# CYM1A113.net
KiCad netlist of a schematic drawn in EAGLE
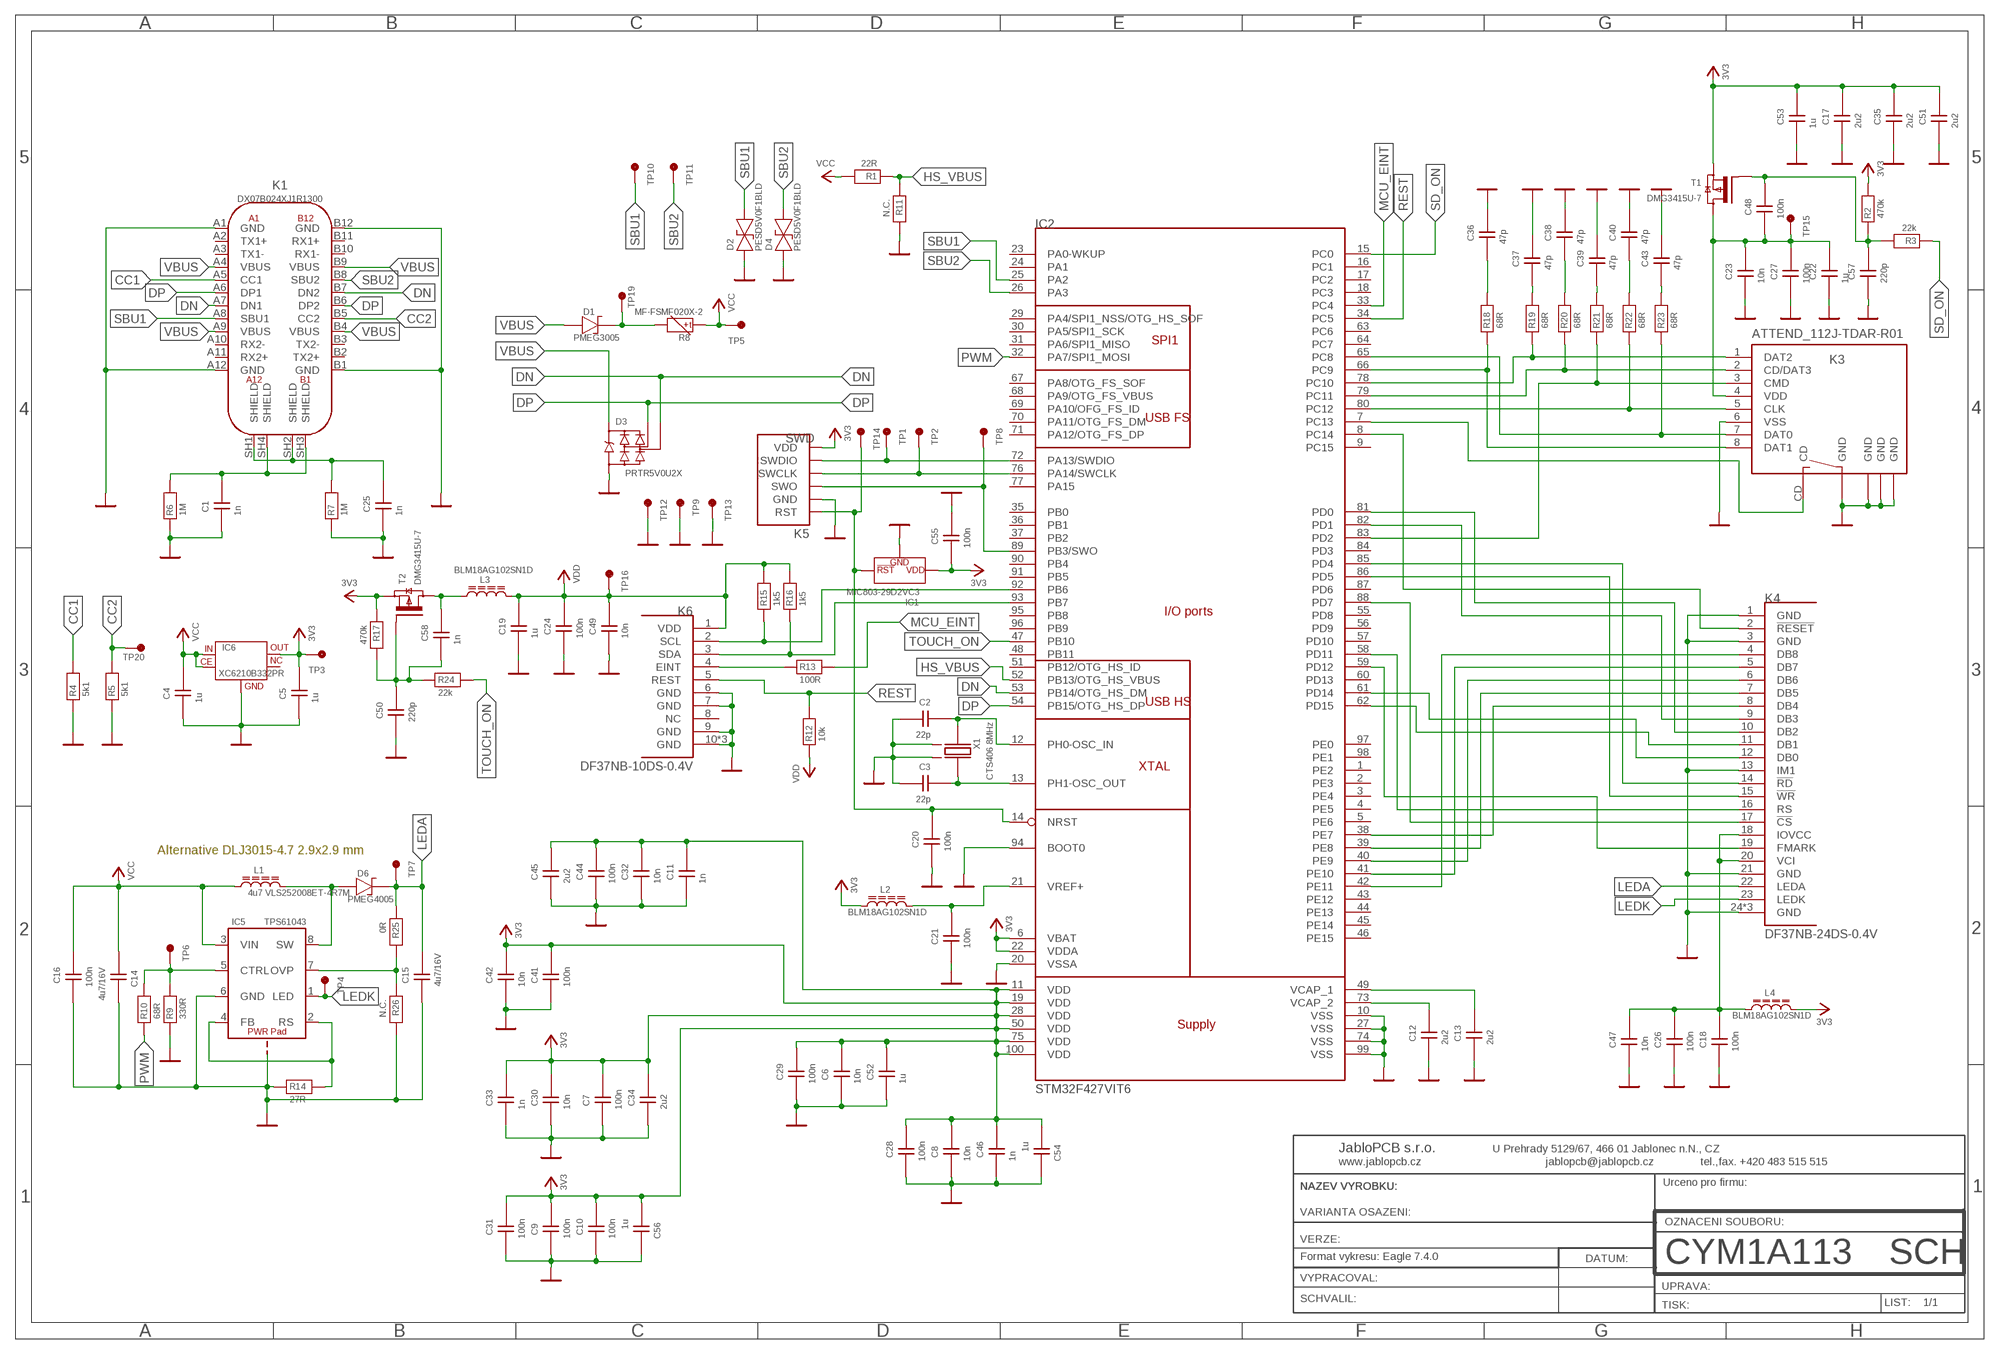
[diagram p0: schematic, sheet 1]

(export (version "E")
  (design (tool "Eeschema 10.0.6"))
  (components
    (comp (ref "C1")
      (value "1n")
      (footprint "eagle-import:0402")
      (libsource (lib "eagle-import") (part "C_0402"))
    )
    (comp (ref "C2")
      (value "22p")
      (footprint "eagle-import:0402")
      (libsource (lib "eagle-import") (part "C_0402"))
    )
    (comp (ref "C3")
      (value "22p")
      (footprint "eagle-import:0402")
      (libsource (lib "eagle-import") (part "C_0402"))
    )
    (comp (ref "C4")
      (value "1u")
      (footprint "eagle-import:0603_REFLOW")
      (libsource (lib "eagle-import") (part "C_0603$REFLOW"))
    )
    (comp (ref "C5")
      (value "1u")
      (footprint "eagle-import:0603")
      (libsource (lib "eagle-import") (part "C_0603"))
    )
    (comp (ref "C6")
      (value "10n")
      (footprint "eagle-import:0402")
      (libsource (lib "eagle-import") (part "C_0402"))
    )
    (comp (ref "C7")
      (value "100n")
      (footprint "eagle-import:0402")
      (libsource (lib "eagle-import") (part "C_0402"))
    )
    (comp (ref "C8")
      (value "10n")
      (footprint "eagle-import:0402")
      (libsource (lib "eagle-import") (part "C_0402"))
    )
    (comp (ref "C9")
      (value "100n")
      (footprint "eagle-import:0402")
      (libsource (lib "eagle-import") (part "C_0402"))
    )
    (comp (ref "C10")
      (value "100n")
      (footprint "eagle-import:0402")
      (libsource (lib "eagle-import") (part "C_0402"))
    )
    (comp (ref "C11")
      (value "1n")
      (footprint "eagle-import:0402")
      (libsource (lib "eagle-import") (part "C_0402"))
    )
    (comp (ref "C12")
      (value "2u2")
      (footprint "eagle-import:0805_REFLOW")
      (libsource (lib "eagle-import") (part "C_0805$REFLOW"))
    )
    (comp (ref "C13")
      (value "2u2")
      (footprint "eagle-import:0805_REFLOW")
      (libsource (lib "eagle-import") (part "C_0805$REFLOW"))
    )
    (comp (ref "C14")
      (value "4u7/16V")
      (footprint "eagle-import:0805_REFLOW")
      (libsource (lib "eagle-import") (part "C_0805$REFLOW"))
    )
    (comp (ref "C15")
      (value "4u7/16V")
      (footprint "eagle-import:0805_REFLOW")
      (libsource (lib "eagle-import") (part "C_0805$REFLOW"))
    )
    (comp (ref "C16")
      (value "100n")
      (footprint "eagle-import:0402")
      (libsource (lib "eagle-import") (part "C_0402"))
    )
    (comp (ref "C17")
      (value "2u2")
      (footprint "eagle-import:0805_REFLOW")
      (libsource (lib "eagle-import") (part "C_0805$REFLOW"))
    )
    (comp (ref "C18")
      (value "100n")
      (footprint "eagle-import:0402")
      (libsource (lib "eagle-import") (part "C_0402"))
    )
    (comp (ref "C19")
      (value "1u")
      (footprint "eagle-import:0603_REFLOW")
      (libsource (lib "eagle-import") (part "C_0603$REFLOW"))
    )
    (comp (ref "C20")
      (value "100n")
      (footprint "eagle-import:0402")
      (libsource (lib "eagle-import") (part "C_0402"))
    )
    (comp (ref "C21")
      (value "100n")
      (footprint "eagle-import:0402")
      (libsource (lib "eagle-import") (part "C_0402"))
    )
    (comp (ref "C22")
      (value "1u")
      (footprint "eagle-import:0603_REFLOW")
      (libsource (lib "eagle-import") (part "C_0603$REFLOW"))
    )
    (comp (ref "C23")
      (value "10n")
      (footprint "eagle-import:0402")
      (libsource (lib "eagle-import") (part "C_0402"))
    )
    (comp (ref "C24")
      (value "100n")
      (footprint "eagle-import:0402")
      (libsource (lib "eagle-import") (part "C_0402"))
    )
    (comp (ref "C25")
      (value "1n")
      (footprint "eagle-import:0402")
      (libsource (lib "eagle-import") (part "C_0402"))
    )
    (comp (ref "C26")
      (value "100n")
      (footprint "eagle-import:0402")
      (libsource (lib "eagle-import") (part "C_0402"))
    )
    (comp (ref "C27")
      (value "100n")
      (footprint "eagle-import:0402")
      (libsource (lib "eagle-import") (part "C_0402"))
    )
    (comp (ref "C28")
      (value "100n")
      (footprint "eagle-import:0402")
      (libsource (lib "eagle-import") (part "C_0402"))
    )
    (comp (ref "C29")
      (value "100n")
      (footprint "eagle-import:0402")
      (libsource (lib "eagle-import") (part "C_0402"))
    )
    (comp (ref "C30")
      (value "10n")
      (footprint "eagle-import:0402")
      (libsource (lib "eagle-import") (part "C_0402"))
    )
    (comp (ref "C31")
      (value "100n")
      (footprint "eagle-import:0402")
      (libsource (lib "eagle-import") (part "C_0402"))
    )
    (comp (ref "C32")
      (value "10n")
      (footprint "eagle-import:0402")
      (libsource (lib "eagle-import") (part "C_0402"))
    )
    (comp (ref "C33")
      (value "1n")
      (footprint "eagle-import:0402")
      (libsource (lib "eagle-import") (part "C_0402"))
    )
    (comp (ref "C34")
      (value "2u2")
      (footprint "eagle-import:0805_REFLOW")
      (libsource (lib "eagle-import") (part "C_0805$REFLOW"))
    )
    (comp (ref "C35")
      (value "2u2")
      (footprint "eagle-import:0805_REFLOW")
      (libsource (lib "eagle-import") (part "C_0805$REFLOW"))
    )
    (comp (ref "C36")
      (value "47p")
      (footprint "eagle-import:0402")
      (libsource (lib "eagle-import") (part "C_0402"))
    )
    (comp (ref "C37")
      (value "47p")
      (footprint "eagle-import:0402")
      (libsource (lib "eagle-import") (part "C_0402"))
    )
    (comp (ref "C38")
      (value "47p")
      (footprint "eagle-import:0402")
      (libsource (lib "eagle-import") (part "C_0402"))
    )
    (comp (ref "C39")
      (value "47p")
      (footprint "eagle-import:0402")
      (libsource (lib "eagle-import") (part "C_0402"))
    )
    (comp (ref "C40")
      (value "47p")
      (footprint "eagle-import:0402")
      (libsource (lib "eagle-import") (part "C_0402"))
    )
    (comp (ref "C41")
      (value "100n")
      (footprint "eagle-import:0402")
      (libsource (lib "eagle-import") (part "C_0402"))
    )
    (comp (ref "C42")
      (value "10n")
      (footprint "eagle-import:0402")
      (libsource (lib "eagle-import") (part "C_0402"))
    )
    (comp (ref "C43")
      (value "47p")
      (footprint "eagle-import:0402")
      (libsource (lib "eagle-import") (part "C_0402"))
    )
    (comp (ref "C44")
      (value "100n")
      (footprint "eagle-import:0402")
      (libsource (lib "eagle-import") (part "C_0402"))
    )
    (comp (ref "C45")
      (value "2u2")
      (footprint "eagle-import:0805_REFLOW")
      (libsource (lib "eagle-import") (part "C_0805$REFLOW"))
    )
    (comp (ref "C46")
      (value "1n")
      (footprint "eagle-import:0402")
      (libsource (lib "eagle-import") (part "C_0402"))
    )
    (comp (ref "C47")
      (value "10n")
      (footprint "eagle-import:0402")
      (libsource (lib "eagle-import") (part "C_0402"))
    )
    (comp (ref "C48")
      (value "100n")
      (footprint "eagle-import:0402")
      (libsource (lib "eagle-import") (part "C_0402"))
    )
    (comp (ref "C49")
      (value "10n")
      (footprint "eagle-import:0402")
      (libsource (lib "eagle-import") (part "C_0402"))
    )
    (comp (ref "C50")
      (value "220p")
      (footprint "eagle-import:0402")
      (libsource (lib "eagle-import") (part "C_0402"))
    )
    (comp (ref "C51")
      (value "2u2")
      (footprint "eagle-import:0805_REFLOW")
      (libsource (lib "eagle-import") (part "C_0805$REFLOW"))
    )
    (comp (ref "C52")
      (value "1u")
      (footprint "eagle-import:0603_REFLOW")
      (libsource (lib "eagle-import") (part "C_0603$REFLOW"))
    )
    (comp (ref "C53")
      (value "1u")
      (footprint "eagle-import:0603_REFLOW")
      (libsource (lib "eagle-import") (part "C_0603$REFLOW"))
    )
    (comp (ref "C54")
      (value "1u")
      (footprint "eagle-import:0603_REFLOW")
      (libsource (lib "eagle-import") (part "C_0603$REFLOW"))
    )
    (comp (ref "C55")
      (value "100n")
      (footprint "eagle-import:0402")
      (libsource (lib "eagle-import") (part "C_0402"))
    )
    (comp (ref "C56")
      (value "1u")
      (footprint "eagle-import:0603_REFLOW")
      (libsource (lib "eagle-import") (part "C_0603$REFLOW"))
    )
    (comp (ref "C57")
      (value "220p")
      (footprint "eagle-import:0402")
      (libsource (lib "eagle-import") (part "C_0402"))
    )
    (comp (ref "C58")
      (value "1n")
      (footprint "eagle-import:0402")
      (libsource (lib "eagle-import") (part "C_0402"))
    )
    (comp (ref "D1")
      (value "PMEG3005")
      (footprint "eagle-import:SOD323F")
      (libsource (lib "eagle-import") (part "DS_SOD323F"))
    )
    (comp (ref "D2")
      (value "PESD5V0F1BLD")
      (footprint "eagle-import:SOD882D")
      (libsource (lib "eagle-import") (part "D_TRANSIL_BI_SOD882D"))
    )
    (comp (ref "D3")
      (value "PRTR5V0U2X")
      (footprint "eagle-import:SOT143B_REFLOW")
      (libsource (lib "eagle-import") (part "PRTR5V0_SOT143B$REFLOW"))
    )
    (comp (ref "D4")
      (value "PESD5V0F1BLD")
      (footprint "eagle-import:SOD882D")
      (libsource (lib "eagle-import") (part "D_TRANSIL_BI_SOD882D"))
    )
    (comp (ref "D6")
      (value "PMEG4005")
      (footprint "eagle-import:SOD323F")
      (libsource (lib "eagle-import") (part "DS_SOD323F"))
    )
    (comp (ref "IC1")
      (value "MIC803-29D2VC3")
      (footprint "eagle-import:SOT23_MEDIUM_SIZE")
      (libsource (lib "eagle-import") (part "MIC803"))
    )
    (comp (ref "IC2")
      (value "STM32F427VIT6")
      (footprint "eagle-import:LQFP100_NO_CENTER_NO_TDOCU")
      (libsource (lib "eagle-import") (part "STM32F427_LQFP100"))
    )
    (comp (ref "IC5")
      (value "TPS61043")
      (footprint "eagle-import:WSON-8_3X3MM")
      (libsource (lib "eagle-import") (part "TP6104X_WSON-8_3X3MM"))
    )
    (comp (ref "IC6")
      (value "XC6210B332PR")
      (footprint "eagle-import:SOT89-5")
      (libsource (lib "eagle-import") (part "XC6210B_SOT89-5"))
    )
    (comp (ref "K1")
      (value "DX07B024XJ1R1300")
      (footprint "eagle-import:USB_C_JAE_DX07B024XJ1")
      (libsource (lib "eagle-import") (part "USB-C_JAE_DX07B024XJ1"))
    )
    (comp (ref "K3")
      (value "ATTEND_112J-TDAR-R01")
      (footprint "eagle-import:ATTEND_112J-TXAR-R01_SMALL")
      (libsource (lib "eagle-import") (part "KON_µSD_CARD_ATTEND_112J_TXAR_R01_SMALL"))
    )
    (comp (ref "K4")
      (value "DF37NB-24DS-0.4V")
      (footprint "eagle-import:DF37NB-24DS-0.4V")
      (libsource (lib "eagle-import") (part "DISPLEJ_154A2411CTP01"))
    )
    (comp (ref "K5")
      (value "SWD")
      (footprint "eagle-import:SWD")
      (libsource (lib "eagle-import") (part "SWD"))
    )
    (comp (ref "K6")
      (value "DF37NB-10DS-0.4V")
      (footprint "eagle-import:DF37NB-10DS-0.4V")
      (libsource (lib "eagle-import") (part "DISPLEJ_154A2411CTP01_TOUCH"))
    )
    (comp (ref "L1")
      (value "4u7 VLS252008ET-4R7M")
      (footprint "eagle-import:L_2.5X2.0")
      (libsource (lib "eagle-import") (part "L_2.5X2.0"))
    )
    (comp (ref "L2")
      (value "BLM18AG102SN1D")
      (footprint "eagle-import:0603_REFLOW")
      (libsource (lib "eagle-import") (part "L_0603$REFLOW"))
    )
    (comp (ref "L3")
      (value "BLM18AG102SN1D")
      (footprint "eagle-import:0603_REFLOW")
      (libsource (lib "eagle-import") (part "L_0603$REFLOW"))
    )
    (comp (ref "L4")
      (value "BLM18AG102SN1D")
      (footprint "eagle-import:0603_REFLOW")
      (libsource (lib "eagle-import") (part "L_0603$REFLOW"))
    )
    (comp (ref "R1")
      (value "22R")
      (footprint "eagle-import:0402")
      (libsource (lib "eagle-import") (part "R_0402"))
    )
    (comp (ref "R2")
      (value "470k")
      (footprint "eagle-import:0402")
      (libsource (lib "eagle-import") (part "R_0402"))
    )
    (comp (ref "R3")
      (value "22k")
      (footprint "eagle-import:0402")
      (libsource (lib "eagle-import") (part "R_0402"))
    )
    (comp (ref "R4")
      (value "5k1")
      (footprint "eagle-import:0402")
      (libsource (lib "eagle-import") (part "R_0402"))
    )
    (comp (ref "R5")
      (value "5k1")
      (footprint "eagle-import:0402")
      (libsource (lib "eagle-import") (part "R_0402"))
    )
    (comp (ref "R6")
      (value "1M")
      (footprint "eagle-import:0402")
      (libsource (lib "eagle-import") (part "R_0402"))
    )
    (comp (ref "R7")
      (value "1M")
      (footprint "eagle-import:0402")
      (libsource (lib "eagle-import") (part "R_0402"))
    )
    (comp (ref "R8")
      (value "MF-FSMF020X-2")
      (footprint "eagle-import:0603")
      (libsource (lib "eagle-import") (part "POLYSWITCH_0603"))
    )
    (comp (ref "R9")
      (value "330R")
      (footprint "eagle-import:0402")
      (libsource (lib "eagle-import") (part "R_0402"))
    )
    (comp (ref "R10")
      (value "68R")
      (footprint "eagle-import:0402")
      (libsource (lib "eagle-import") (part "R_0402"))
    )
    (comp (ref "R11")
      (value "N.C.")
      (footprint "eagle-import:0402")
      (libsource (lib "eagle-import") (part "R_0402"))
    )
    (comp (ref "R12")
      (value "10k")
      (footprint "eagle-import:0402")
      (libsource (lib "eagle-import") (part "R_0402"))
    )
    (comp (ref "R13")
      (value "100R")
      (footprint "eagle-import:0402")
      (libsource (lib "eagle-import") (part "R_0402"))
    )
    (comp (ref "R14")
      (value "27R")
      (footprint "eagle-import:0402")
      (libsource (lib "eagle-import") (part "R_0402"))
    )
    (comp (ref "R15")
      (value "1k5")
      (footprint "eagle-import:0402")
      (libsource (lib "eagle-import") (part "R_0402"))
    )
    (comp (ref "R16")
      (value "1k5")
      (footprint "eagle-import:0402")
      (libsource (lib "eagle-import") (part "R_0402"))
    )
    (comp (ref "R17")
      (value "470k")
      (footprint "eagle-import:0402")
      (libsource (lib "eagle-import") (part "R_0402"))
    )
    (comp (ref "R18")
      (value "68R")
      (footprint "eagle-import:0402")
      (libsource (lib "eagle-import") (part "R_0402"))
    )
    (comp (ref "R19")
      (value "68R")
      (footprint "eagle-import:0402")
      (libsource (lib "eagle-import") (part "R_0402"))
    )
    (comp (ref "R20")
      (value "68R")
      (footprint "eagle-import:0402")
      (libsource (lib "eagle-import") (part "R_0402"))
    )
    (comp (ref "R21")
      (value "68R")
      (footprint "eagle-import:0402")
      (libsource (lib "eagle-import") (part "R_0402"))
    )
    (comp (ref "R22")
      (value "68R")
      (footprint "eagle-import:0402")
      (libsource (lib "eagle-import") (part "R_0402"))
    )
    (comp (ref "R23")
      (value "68R")
      (footprint "eagle-import:0402")
      (libsource (lib "eagle-import") (part "R_0402"))
    )
    (comp (ref "R24")
      (value "22k")
      (footprint "eagle-import:0402")
      (libsource (lib "eagle-import") (part "R_0402"))
    )
    (comp (ref "R25")
      (value "0R")
      (footprint "eagle-import:0402")
      (libsource (lib "eagle-import") (part "R_0402"))
    )
    (comp (ref "R26")
      (value "N.C.")
      (footprint "eagle-import:0402")
      (libsource (lib "eagle-import") (part "R_0402"))
    )
    (comp (ref "T1")
      (value "DMG3415U-7")
      (footprint "eagle-import:SOT23_REFLOW")
      (libsource (lib "eagle-import") (part "PMOS_SOT-23_REF"))
    )
    (comp (ref "T2")
      (value "DMG3415U-7")
      (footprint "eagle-import:SOT23_REFLOW")
      (libsource (lib "eagle-import") (part "PMOS_SOT-23_REF"))
    )
    (comp (ref "TP1")
      (value "MB_1.27")
      (footprint "eagle-import:MB1.27")
      (libsource (lib "eagle-import") (part "MB_1.27"))
    )
    (comp (ref "TP2")
      (value "MB_1.27")
      (footprint "eagle-import:MB1.27")
      (libsource (lib "eagle-import") (part "MB_1.27"))
    )
    (comp (ref "TP3")
      (value "MB_1.50")
      (footprint "eagle-import:MB1.5")
      (libsource (lib "eagle-import") (part "MB_1.50"))
    )
    (comp (ref "TP4")
      (value "MB_1.27")
      (footprint "eagle-import:MB1.27")
      (libsource (lib "eagle-import") (part "MB_1.27"))
    )
    (comp (ref "TP5")
      (value "MB_1.50")
      (footprint "eagle-import:MB1.5")
      (libsource (lib "eagle-import") (part "MB_1.50"))
    )
    (comp (ref "TP6")
      (value "MB_1.27")
      (footprint "eagle-import:MB1.27")
      (libsource (lib "eagle-import") (part "MB_1.27"))
    )
    (comp (ref "TP7")
      (value "MB_1.27")
      (footprint "eagle-import:MB1.27")
      (libsource (lib "eagle-import") (part "MB_1.27"))
    )
    (comp (ref "TP8")
      (value "MB_1.27")
      (footprint "eagle-import:MB1.27")
      (libsource (lib "eagle-import") (part "MB_1.27"))
    )
    (comp (ref "TP9")
      (value "MB_1.27")
      (footprint "eagle-import:MB1.27")
      (libsource (lib "eagle-import") (part "MB_1.27"))
    )
    (comp (ref "TP10")
      (value "MB_1.50")
      (footprint "eagle-import:MB1.5")
      (libsource (lib "eagle-import") (part "MB_1.50"))
    )
    (comp (ref "TP11")
      (value "MB_1.50")
      (footprint "eagle-import:MB1.5")
      (libsource (lib "eagle-import") (part "MB_1.50"))
    )
    (comp (ref "TP12")
      (value "MB_1.27")
      (footprint "eagle-import:MB1.27")
      (libsource (lib "eagle-import") (part "MB_1.27"))
    )
    (comp (ref "TP13")
      (value "MB_1.27")
      (footprint "eagle-import:MB1.27")
      (libsource (lib "eagle-import") (part "MB_1.27"))
    )
    (comp (ref "TP14")
      (value "MB_1.27")
      (footprint "eagle-import:MB1.27")
      (libsource (lib "eagle-import") (part "MB_1.27"))
    )
    (comp (ref "TP15")
      (value "MB_1.27")
      (footprint "eagle-import:MB1.27")
      (libsource (lib "eagle-import") (part "MB_1.27"))
    )
    (comp (ref "TP16")
      (value "MB_1.27")
      (footprint "eagle-import:MB1.27")
      (libsource (lib "eagle-import") (part "MB_1.27"))
    )
    (comp (ref "TP19")
      (value "MB_1.00")
      (footprint "eagle-import:MB_1.00")
      (libsource (lib "eagle-import") (part "MB_1.00"))
    )
    (comp (ref "TP20")
      (value "MB_1.00")
      (footprint "eagle-import:MB_1.00")
      (libsource (lib "eagle-import") (part "MB_1.00"))
    )
    (comp (ref "X1")
      (value "CTS406 8MHz")
      (footprint "eagle-import:X6,0X3,5")
      (libsource (lib "eagle-import") (part "X_4V_6,0X3,5"))
    )
  )
  (nets
    (net (code "1") (name "3V3") (class "Default")
      (node (ref "C10") (pin "P$2") (pinfunction "2_P$2") (pintype "passive"))
      (node (ref "C11") (pin "P$2") (pinfunction "2_P$2") (pintype "passive"))
      (node (ref "C17") (pin "2") (pinfunction "2_2") (pintype "passive"))
      (node (ref "C28") (pin "P$2") (pinfunction "2_P$2") (pintype "passive"))
      (node (ref "C29") (pin "P$2") (pinfunction "2_P$2") (pintype "passive"))
      (node (ref "C30") (pin "P$2") (pinfunction "2_P$2") (pintype "passive"))
      (node (ref "C31") (pin "P$2") (pinfunction "2_P$2") (pintype "passive"))
      (node (ref "C32") (pin "P$2") (pinfunction "2_P$2") (pintype "passive"))
      (node (ref "C33") (pin "P$2") (pinfunction "2_P$2") (pintype "passive"))
      (node (ref "C34") (pin "2") (pinfunction "2_2") (pintype "passive"))
      (node (ref "C35") (pin "2") (pinfunction "2_2") (pintype "passive"))
      (node (ref "C41") (pin "P$2") (pinfunction "2_P$2") (pintype "passive"))
      (node (ref "C42") (pin "P$2") (pinfunction "2_P$2") (pintype "passive"))
      (node (ref "C44") (pin "P$2") (pinfunction "2_P$2") (pintype "passive"))
      (node (ref "C45") (pin "2") (pinfunction "2_2") (pintype "passive"))
      (node (ref "C46") (pin "P$2") (pinfunction "2_P$2") (pintype "passive"))
      (node (ref "C5") (pin "2") (pinfunction "2_2") (pintype "passive"))
      (node (ref "C51") (pin "2") (pinfunction "2_2") (pintype "passive"))
      (node (ref "C52") (pin "2") (pinfunction "2_2") (pintype "passive"))
      (node (ref "C53") (pin "2") (pinfunction "2_2") (pintype "passive"))
      (node (ref "C54") (pin "1") (pinfunction "1_1") (pintype "passive"))
      (node (ref "C55") (pin "P$1") (pinfunction "1_P$1") (pintype "passive"))
      (node (ref "C56") (pin "1") (pinfunction "1_1") (pintype "passive"))
      (node (ref "C6") (pin "P$2") (pinfunction "2_P$2") (pintype "passive"))
      (node (ref "C7") (pin "P$2") (pinfunction "2_P$2") (pintype "passive"))
      (node (ref "C8") (pin "P$2") (pinfunction "2_P$2") (pintype "passive"))
      (node (ref "C9") (pin "P$2") (pinfunction "2_P$2") (pintype "passive"))
      (node (ref "IC1") (pin "3") (pinfunction "VDD_3") (pintype "passive"))
      (node (ref "IC2") (pin "100") (pinfunction "VDD_100") (pintype "power_in"))
      (node (ref "IC2") (pin "11") (pinfunction "VDD_11") (pintype "power_in"))
      (node (ref "IC2") (pin "19") (pinfunction "VDD_19") (pintype "power_in"))
      (node (ref "IC2") (pin "22") (pinfunction "VDDA_22") (pintype "power_in"))
      (node (ref "IC2") (pin "28") (pinfunction "VDD_28") (pintype "power_in"))
      (node (ref "IC2") (pin "50") (pinfunction "VDD_50") (pintype "power_in"))
      (node (ref "IC2") (pin "6") (pinfunction "VBAT_6") (pintype "power_in"))
      (node (ref "IC2") (pin "75") (pinfunction "VDD_75") (pintype "power_in"))
      (node (ref "IC6") (pin "5") (pinfunction "OUT_5") (pintype "passive"))
      (node (ref "K5") (pin "VCC") (pinfunction "VDD_VCC") (pintype "passive"))
      (node (ref "L2") (pin "1") (pinfunction "1_1") (pintype "passive"))
      (node (ref "L4") (pin "2") (pinfunction "2_2") (pintype "passive"))
      (node (ref "R17") (pin "P$1") (pinfunction "1_P$1") (pintype "passive"))
      (node (ref "R2") (pin "P$2") (pinfunction "2_P$2") (pintype "passive"))
      (node (ref "T1") (pin "1") (pinfunction "S_1") (pintype "passive"))
      (node (ref "T2") (pin "1") (pinfunction "S_1") (pintype "passive"))
      (node (ref "TP3") (pin "1") (pinfunction "1_1") (pintype "passive"))
    )
    (net (code "2") (name "CC1") (class "Default")
      (node (ref "K1") (pin "A5") (pinfunction "CC1_A5") (pintype "passive"))
      (node (ref "R4") (pin "P$2") (pinfunction "2_P$2") (pintype "passive"))
    )
    (net (code "3") (name "CC2") (class "Default")
      (node (ref "K1") (pin "B5") (pinfunction "CC2_B5") (pintype "passive"))
      (node (ref "R5") (pin "P$2") (pinfunction "2_P$2") (pintype "passive"))
      (node (ref "TP20") (pin "1") (pinfunction "1_1") (pintype "passive"))
    )
    (net (code "4") (name "DN") (class "Default")
      (node (ref "D3") (pin "3") (pinfunction "I/O2_3") (pintype "passive"))
      (node (ref "IC2") (pin "53") (pinfunction "PB14/OTG_HS_DM_53") (pintype "bidirectional"))
      (node (ref "K1") (pin "A7") (pinfunction "DN1_A7") (pintype "passive"))
      (node (ref "K1") (pin "B7") (pinfunction "DN2_B7") (pintype "passive"))
    )
    (net (code "5") (name "DP") (class "Default")
      (node (ref "D3") (pin "2") (pinfunction "I/O1_2") (pintype "passive"))
      (node (ref "IC2") (pin "54") (pinfunction "PB15/OTG_HS_DP_54") (pintype "bidirectional"))
      (node (ref "K1") (pin "A6") (pinfunction "DP1_A6") (pintype "passive"))
      (node (ref "K1") (pin "B6") (pinfunction "DP2_B6") (pintype "passive"))
    )
    (net (code "6") (name "GND") (class "Default")
      (node (ref "C1") (pin "P$1") (pinfunction "1_P$1") (pintype "passive"))
      (node (ref "C10") (pin "P$1") (pinfunction "1_P$1") (pintype "passive"))
      (node (ref "C11") (pin "P$1") (pinfunction "1_P$1") (pintype "passive"))
      (node (ref "C12") (pin "1") (pinfunction "1_1") (pintype "passive"))
      (node (ref "C13") (pin "1") (pinfunction "1_1") (pintype "passive"))
      (node (ref "C14") (pin "2") (pinfunction "2_2") (pintype "passive"))
      (node (ref "C15") (pin "1") (pinfunction "1_1") (pintype "passive"))
      (node (ref "C16") (pin "P$1") (pinfunction "1_P$1") (pintype "passive"))
      (node (ref "C17") (pin "1") (pinfunction "1_1") (pintype "passive"))
      (node (ref "C18") (pin "P$1") (pinfunction "1_P$1") (pintype "passive"))
      (node (ref "C19") (pin "1") (pinfunction "1_1") (pintype "passive"))
      (node (ref "C2") (pin "P$1") (pinfunction "1_P$1") (pintype "passive"))
      (node (ref "C20") (pin "P$1") (pinfunction "1_P$1") (pintype "passive"))
      (node (ref "C21") (pin "P$1") (pinfunction "1_P$1") (pintype "passive"))
      (node (ref "C22") (pin "1") (pinfunction "1_1") (pintype "passive"))
      (node (ref "C23") (pin "P$1") (pinfunction "1_P$1") (pintype "passive"))
      (node (ref "C24") (pin "P$1") (pinfunction "1_P$1") (pintype "passive"))
      (node (ref "C25") (pin "P$1") (pinfunction "1_P$1") (pintype "passive"))
      (node (ref "C26") (pin "P$1") (pinfunction "1_P$1") (pintype "passive"))
      (node (ref "C27") (pin "P$1") (pinfunction "1_P$1") (pintype "passive"))
      (node (ref "C28") (pin "P$1") (pinfunction "1_P$1") (pintype "passive"))
      (node (ref "C29") (pin "P$1") (pinfunction "1_P$1") (pintype "passive"))
      (node (ref "C3") (pin "P$1") (pinfunction "1_P$1") (pintype "passive"))
      (node (ref "C30") (pin "P$1") (pinfunction "1_P$1") (pintype "passive"))
      (node (ref "C31") (pin "P$1") (pinfunction "1_P$1") (pintype "passive"))
      (node (ref "C32") (pin "P$1") (pinfunction "1_P$1") (pintype "passive"))
      (node (ref "C33") (pin "P$1") (pinfunction "1_P$1") (pintype "passive"))
      (node (ref "C34") (pin "1") (pinfunction "1_1") (pintype "passive"))
      (node (ref "C35") (pin "1") (pinfunction "1_1") (pintype "passive"))
      (node (ref "C36") (pin "P$2") (pinfunction "2_P$2") (pintype "passive"))
      (node (ref "C37") (pin "P$2") (pinfunction "2_P$2") (pintype "passive"))
      (node (ref "C38") (pin "P$2") (pinfunction "2_P$2") (pintype "passive"))
      (node (ref "C39") (pin "P$2") (pinfunction "2_P$2") (pintype "passive"))
      (node (ref "C4") (pin "1") (pinfunction "1_1") (pintype "passive"))
      (node (ref "C40") (pin "P$2") (pinfunction "2_P$2") (pintype "passive"))
      (node (ref "C41") (pin "P$1") (pinfunction "1_P$1") (pintype "passive"))
      (node (ref "C42") (pin "P$1") (pinfunction "1_P$1") (pintype "passive"))
      (node (ref "C43") (pin "P$2") (pinfunction "2_P$2") (pintype "passive"))
      (node (ref "C44") (pin "P$1") (pinfunction "1_P$1") (pintype "passive"))
      (node (ref "C45") (pin "1") (pinfunction "1_1") (pintype "passive"))
      (node (ref "C46") (pin "P$1") (pinfunction "1_P$1") (pintype "passive"))
      (node (ref "C47") (pin "P$1") (pinfunction "1_P$1") (pintype "passive"))
      (node (ref "C49") (pin "P$1") (pinfunction "1_P$1") (pintype "passive"))
      (node (ref "C5") (pin "1") (pinfunction "1_1") (pintype "passive"))
      (node (ref "C50") (pin "P$1") (pinfunction "1_P$1") (pintype "passive"))
      (node (ref "C51") (pin "1") (pinfunction "1_1") (pintype "passive"))
      (node (ref "C52") (pin "1") (pinfunction "1_1") (pintype "passive"))
      (node (ref "C53") (pin "1") (pinfunction "1_1") (pintype "passive"))
      (node (ref "C54") (pin "2") (pinfunction "2_2") (pintype "passive"))
      (node (ref "C55") (pin "P$2") (pinfunction "2_P$2") (pintype "passive"))
      (node (ref "C56") (pin "2") (pinfunction "2_2") (pintype "passive"))
      (node (ref "C57") (pin "P$1") (pinfunction "1_P$1") (pintype "passive"))
      (node (ref "C6") (pin "P$1") (pinfunction "1_P$1") (pintype "passive"))
      (node (ref "C7") (pin "P$1") (pinfunction "1_P$1") (pintype "passive"))
      (node (ref "C8") (pin "P$1") (pinfunction "1_P$1") (pintype "passive"))
      (node (ref "C9") (pin "P$1") (pinfunction "1_P$1") (pintype "passive"))
      (node (ref "D2") (pin "1") (pinfunction "1_1") (pintype "passive"))
      (node (ref "D3") (pin "1") (pinfunction "GND_1") (pintype "passive"))
      (node (ref "D4") (pin "1") (pinfunction "1_1") (pintype "passive"))
      (node (ref "IC1") (pin "1") (pinfunction "GND_1") (pintype "passive"))
      (node (ref "IC2") (pin "10") (pinfunction "VSS_10") (pintype "power_in"))
      (node (ref "IC2") (pin "20") (pinfunction "VSSA_20") (pintype "power_in"))
      (node (ref "IC2") (pin "27") (pinfunction "VSS_27") (pintype "power_in"))
      (node (ref "IC2") (pin "74") (pinfunction "VSS_74") (pintype "power_in"))
      (node (ref "IC2") (pin "94") (pinfunction "BOOT0_94") (pintype "input"))
      (node (ref "IC2") (pin "99") (pinfunction "VSS_99") (pintype "power_in"))
      (node (ref "IC5") (pin "6") (pinfunction "GND_6") (pintype "power_in"))
      (node (ref "IC5") (pin "EP") (pinfunction "EP_EP") (pintype "passive"))
      (node (ref "IC5") (pin "EP$1") (pinfunction "EP_EP$1") (pintype "passive"))
      (node (ref "IC5") (pin "EP$2") (pinfunction "EP_EP$2") (pintype "passive"))
      (node (ref "IC5") (pin "EP$3") (pinfunction "EP_EP$3") (pintype "passive"))
      (node (ref "IC5") (pin "EP$4") (pinfunction "EP_EP$4") (pintype "passive"))
      (node (ref "IC6") (pin "2") (pinfunction "GND_2") (pintype "passive"))
      (node (ref "K1") (pin "A1") (pinfunction "GND_A1") (pintype "passive"))
      (node (ref "K1") (pin "A12") (pinfunction "GND_A12") (pintype "passive"))
      (node (ref "K1") (pin "B1") (pinfunction "GND_B1") (pintype "passive"))
      (node (ref "K1") (pin "B12") (pinfunction "GND_B12") (pintype "passive"))
      (node (ref "K3") (pin "6") (pinfunction "VSS_6") (pintype "bidirectional"))
      (node (ref "K3") (pin "GND@1") (pinfunction "GND_GND@1") (pintype "power_in"))
      (node (ref "K3") (pin "GND@2") (pinfunction "GND_GND@2") (pintype "power_in"))
      (node (ref "K3") (pin "GND@3") (pinfunction "GND_GND@3") (pintype "power_in"))
      (node (ref "K3") (pin "GND@4") (pinfunction "GND_GND@4") (pintype "power_in"))
      (node (ref "K4") (pin "1") (pinfunction "GND_1") (pintype "power_in"))
      (node (ref "K4") (pin "13") (pinfunction "IM1_13") (pintype "bidirectional"))
      (node (ref "K4") (pin "21") (pinfunction "GND_21") (pintype "power_in"))
      (node (ref "K4") (pin "24") (pinfunction "GND_24") (pintype "power_in"))
      (node (ref "K4") (pin "25") (pinfunction "GND_25") (pintype "power_in"))
      (node (ref "K4") (pin "26") (pinfunction "GND_26") (pintype "power_in"))
      (node (ref "K4") (pin "3") (pinfunction "GND_3") (pintype "power_in"))
      (node (ref "K5") (pin "GND") (pinfunction "GND_GND") (pintype "passive"))
      (node (ref "K6") (pin "10") (pinfunction "GND_10") (pintype "power_in"))
      (node (ref "K6") (pin "11") (pinfunction "GND_11") (pintype "power_in"))
      (node (ref "K6") (pin "12") (pinfunction "GND_12") (pintype "power_in"))
      (node (ref "K6") (pin "6") (pinfunction "GND_6") (pintype "power_in"))
      (node (ref "K6") (pin "7") (pinfunction "GND_7") (pintype "power_in"))
      (node (ref "K6") (pin "9") (pinfunction "GND_9") (pintype "power_in"))
      (node (ref "R11") (pin "P$2") (pinfunction "2_P$2") (pintype "passive"))
      (node (ref "R14") (pin "P$1") (pinfunction "1_P$1") (pintype "passive"))
      (node (ref "R26") (pin "P$2") (pinfunction "2_P$2") (pintype "passive"))
      (node (ref "R4") (pin "P$1") (pinfunction "1_P$1") (pintype "passive"))
      (node (ref "R5") (pin "P$1") (pinfunction "1_P$1") (pintype "passive"))
      (node (ref "R6") (pin "P$1") (pinfunction "1_P$1") (pintype "passive"))
      (node (ref "R7") (pin "P$1") (pinfunction "1_P$1") (pintype "passive"))
      (node (ref "R9") (pin "P$1") (pinfunction "1_P$1") (pintype "passive"))
      (node (ref "TP12") (pin "1") (pinfunction "1_1") (pintype "passive"))
      (node (ref "TP13") (pin "1") (pinfunction "1_1") (pintype "passive"))
      (node (ref "TP9") (pin "1") (pinfunction "1_1") (pintype "passive"))
      (node (ref "X1") (pin "2") (pinfunction "GND1_2") (pintype "passive"))
      (node (ref "X1") (pin "4") (pinfunction "GND2_4") (pintype "passive"))
    )
    (net (code "7") (name "HS_VBUS") (class "Default")
      (node (ref "IC2") (pin "52") (pinfunction "PB13/OTG_HS_VBUS_52") (pintype "bidirectional"))
      (node (ref "R1") (pin "P$1") (pinfunction "1_P$1") (pintype "passive"))
      (node (ref "R11") (pin "P$1") (pinfunction "1_P$1") (pintype "passive"))
    )
    (net (code "8") (name "LEDA") (class "Default")
      (node (ref "C15") (pin "2") (pinfunction "2_2") (pintype "passive"))
      (node (ref "D6") (pin "K") (pinfunction "2_K") (pintype "passive"))
      (node (ref "K4") (pin "22") (pinfunction "LEDA_22") (pintype "passive"))
      (node (ref "R25") (pin "P$1") (pinfunction "1_P$1") (pintype "passive"))
      (node (ref "TP7") (pin "1") (pinfunction "1_1") (pintype "passive"))
    )
    (net (code "9") (name "LEDK") (class "Default")
      (node (ref "IC5") (pin "1") (pinfunction "LED_1") (pintype "passive"))
      (node (ref "K4") (pin "23") (pinfunction "LEDK_23") (pintype "passive"))
      (node (ref "TP4") (pin "1") (pinfunction "1_1") (pintype "passive"))
    )
    (net (code "10") (name "MCU_EINT") (class "Default")
      (node (ref "IC2") (pin "33") (pinfunction "PC4_33") (pintype "bidirectional"))
      (node (ref "R13") (pin "P$2") (pinfunction "2_P$2") (pintype "passive"))
    )
    (net (code "11") (name "Net-(C1-2)") (class "Default")
      (node (ref "C1") (pin "P$2") (pinfunction "2_P$2") (pintype "passive"))
      (node (ref "K1") (pin "SH3") (pinfunction "SHIELD_SH3") (pintype "passive"))
      (node (ref "K1") (pin "SH4") (pinfunction "SHIELD_SH4") (pintype "passive"))
      (node (ref "R6") (pin "P$2") (pinfunction "2_P$2") (pintype "passive"))
    )
    (net (code "12") (name "Net-(C2-2)") (class "Default")
      (node (ref "C2") (pin "P$2") (pinfunction "2_P$2") (pintype "passive"))
      (node (ref "IC2") (pin "12") (pinfunction "PH0-OSC_IN_12") (pintype "input"))
      (node (ref "X1") (pin "1") (pinfunction "1_1") (pintype "passive"))
    )
    (net (code "13") (name "Net-(C3-2)") (class "Default")
      (node (ref "C3") (pin "P$2") (pinfunction "2_P$2") (pintype "passive"))
      (node (ref "IC2") (pin "13") (pinfunction "PH1-OSC_OUT_13") (pintype "output"))
      (node (ref "X1") (pin "3") (pinfunction "2_3") (pintype "passive"))
    )
    (net (code "14") (name "Net-(C18-2)") (class "Default")
      (node (ref "C18") (pin "P$2") (pinfunction "2_P$2") (pintype "passive"))
      (node (ref "C26") (pin "P$2") (pinfunction "2_P$2") (pintype "passive"))
      (node (ref "C47") (pin "P$2") (pinfunction "2_P$2") (pintype "passive"))
      (node (ref "K4") (pin "18") (pinfunction "IOVCC_18") (pintype "power_in"))
      (node (ref "K4") (pin "20") (pinfunction "VCI_20") (pintype "passive"))
      (node (ref "L4") (pin "1") (pinfunction "1_1") (pintype "passive"))
    )
    (net (code "15") (name "Net-(C20-2)") (class "Default")
      (node (ref "C20") (pin "P$2") (pinfunction "2_P$2") (pintype "passive"))
      (node (ref "IC1") (pin "2") (pinfunction "RES_2") (pintype "passive"))
      (node (ref "IC2") (pin "14") (pinfunction "NRST_14") (pintype "bidirectional"))
      (node (ref "K5") (pin "RST") (pinfunction "RST_RST") (pintype "passive"))
      (node (ref "TP14") (pin "1") (pinfunction "1_1") (pintype "passive"))
    )
    (net (code "16") (name "Net-(C21-2)") (class "Default")
      (node (ref "C21") (pin "P$2") (pinfunction "2_P$2") (pintype "passive"))
      (node (ref "IC2") (pin "21") (pinfunction "VREF+_21") (pintype "power_in"))
      (node (ref "L2") (pin "2") (pinfunction "2_2") (pintype "passive"))
    )
    (net (code "17") (name "Net-(C23-2)") (class "Default")
      (node (ref "C22") (pin "2") (pinfunction "2_2") (pintype "passive"))
      (node (ref "C23") (pin "P$2") (pinfunction "2_P$2") (pintype "passive"))
      (node (ref "C27") (pin "P$2") (pinfunction "2_P$2") (pintype "passive"))
      (node (ref "C48") (pin "P$1") (pinfunction "1_P$1") (pintype "passive"))
      (node (ref "K3") (pin "4") (pinfunction "VDD_4") (pintype "power_in"))
      (node (ref "T1") (pin "3") (pinfunction "D_3") (pintype "passive"))
      (node (ref "TP15") (pin "1") (pinfunction "1_1") (pintype "passive"))
    )
    (net (code "18") (name "Net-(C25-2)") (class "Default")
      (node (ref "C25") (pin "P$2") (pinfunction "2_P$2") (pintype "passive"))
      (node (ref "K1") (pin "SH1") (pinfunction "SHIELD_SH1") (pintype "passive"))
      (node (ref "K1") (pin "SH2") (pinfunction "SHIELD_SH2") (pintype "passive"))
      (node (ref "R7") (pin "P$2") (pinfunction "2_P$2") (pintype "passive"))
    )
    (net (code "19") (name "Net-(C36-1)") (class "Default")
      (node (ref "C36") (pin "P$1") (pinfunction "1_P$1") (pintype "passive"))
      (node (ref "R18") (pin "P$2") (pinfunction "2_P$2") (pintype "passive"))
    )
    (net (code "20") (name "Net-(C37-1)") (class "Default")
      (node (ref "C37") (pin "P$1") (pinfunction "1_P$1") (pintype "passive"))
      (node (ref "R19") (pin "P$2") (pinfunction "2_P$2") (pintype "passive"))
    )
    (net (code "21") (name "Net-(C38-1)") (class "Default")
      (node (ref "C38") (pin "P$1") (pinfunction "1_P$1") (pintype "passive"))
      (node (ref "R20") (pin "P$2") (pinfunction "2_P$2") (pintype "passive"))
    )
    (net (code "22") (name "Net-(C39-1)") (class "Default")
      (node (ref "C39") (pin "P$1") (pinfunction "1_P$1") (pintype "passive"))
      (node (ref "R21") (pin "P$2") (pinfunction "2_P$2") (pintype "passive"))
    )
    (net (code "23") (name "Net-(C40-1)") (class "Default")
      (node (ref "C40") (pin "P$1") (pinfunction "1_P$1") (pintype "passive"))
      (node (ref "R22") (pin "P$2") (pinfunction "2_P$2") (pintype "passive"))
    )
    (net (code "24") (name "Net-(C43-1)") (class "Default")
      (node (ref "C43") (pin "P$1") (pinfunction "1_P$1") (pintype "passive"))
      (node (ref "R23") (pin "P$2") (pinfunction "2_P$2") (pintype "passive"))
    )
    (net (code "25") (name "Net-(C48-2)") (class "Default")
      (node (ref "C48") (pin "P$2") (pinfunction "2_P$2") (pintype "passive"))
      (node (ref "C57") (pin "P$2") (pinfunction "2_P$2") (pintype "passive"))
      (node (ref "R2") (pin "P$1") (pinfunction "1_P$1") (pintype "passive"))
      (node (ref "R3") (pin "P$2") (pinfunction "2_P$2") (pintype "passive"))
      (node (ref "T1") (pin "2") (pinfunction "G_2") (pintype "input"))
    )
    (net (code "26") (name "Net-(C50-2)") (class "Default")
      (node (ref "C50") (pin "P$2") (pinfunction "2_P$2") (pintype "passive"))
      (node (ref "C58") (pin "P$1") (pinfunction "1_P$1") (pintype "passive"))
      (node (ref "R17") (pin "P$2") (pinfunction "2_P$2") (pintype "passive"))
      (node (ref "R24") (pin "P$1") (pinfunction "1_P$1") (pintype "passive"))
      (node (ref "T2") (pin "2") (pinfunction "G_2") (pintype "input"))
    )
    (net (code "27") (name "Net-(C58-2)") (class "Default")
      (node (ref "C58") (pin "P$2") (pinfunction "2_P$2") (pintype "passive"))
      (node (ref "L3") (pin "1") (pinfunction "1_1") (pintype "passive"))
      (node (ref "T2") (pin "3") (pinfunction "D_3") (pintype "passive"))
    )
    (net (code "28") (name "Net-(D1-2)") (class "Default")
      (node (ref "D1") (pin "K") (pinfunction "2_K") (pintype "passive"))
      (node (ref "R8") (pin "2") (pinfunction "2_2") (pintype "passive"))
      (node (ref "TP19") (pin "1") (pinfunction "1_1") (pintype "passive"))
    )
    (net (code "29") (name "Net-(D6-1)") (class "Default")
      (node (ref "D6") (pin "A") (pinfunction "1_A") (pintype "passive"))
      (node (ref "IC5") (pin "8") (pinfunction "SW_8") (pintype "output"))
      (node (ref "L1") (pin "2") (pinfunction "2_2") (pintype "passive"))
    )
    (net (code "30") (name "Net-(IC2-PA13{slash}SWDIO)") (class "Default")
      (node (ref "IC2") (pin "72") (pinfunction "PA13/SWDIO_72") (pintype "bidirectional"))
      (node (ref "K5") (pin "SWDIO") (pinfunction "SWDIO_SWDIO") (pintype "passive"))
      (node (ref "TP1") (pin "1") (pinfunction "1_1") (pintype "passive"))
    )
    (net (code "31") (name "Net-(IC2-PA14{slash}SWCLK)") (class "Default")
      (node (ref "IC2") (pin "76") (pinfunction "PA14/SWCLK_76") (pintype "bidirectional"))
      (node (ref "K5") (pin "SWCLK") (pinfunction "SWCLK_SWCLK") (pintype "passive"))
      (node (ref "TP2") (pin "1") (pinfunction "1_1") (pintype "passive"))
    )
    (net (code "32") (name "Net-(IC2-PB3{slash}SWO)") (class "Default")
      (node (ref "IC2") (pin "89") (pinfunction "PB3/SWO_89") (pintype "bidirectional"))
      (node (ref "K5") (pin "SWO") (pinfunction "SWO_SWO") (pintype "passive"))
      (node (ref "TP8") (pin "1") (pinfunction "1_1") (pintype "passive"))
    )
    (net (code "33") (name "Net-(IC2-PB6)") (class "Default")
      (node (ref "IC2") (pin "92") (pinfunction "PB6_92") (pintype "bidirectional"))
      (node (ref "K6") (pin "2") (pinfunction "SCL_2") (pintype "bidirectional"))
      (node (ref "R15") (pin "P$1") (pinfunction "1_P$1") (pintype "passive"))
    )
    (net (code "34") (name "Net-(IC2-PB7)") (class "Default")
      (node (ref "IC2") (pin "93") (pinfunction "PB7_93") (pintype "bidirectional"))
      (node (ref "K6") (pin "3") (pinfunction "SDA_3") (pintype "bidirectional"))
      (node (ref "R16") (pin "P$1") (pinfunction "1_P$1") (pintype "passive"))
    )
    (net (code "35") (name "Net-(IC2-PC8)") (class "Default")
      (node (ref "IC2") (pin "65") (pinfunction "PC8_65") (pintype "bidirectional"))
      (node (ref "K3") (pin "7") (pinfunction "DAT0_7") (pintype "bidirectional"))
      (node (ref "R23") (pin "P$1") (pinfunction "1_P$1") (pintype "passive"))
    )
    (net (code "36") (name "Net-(IC2-PC9)") (class "Default")
      (node (ref "IC2") (pin "66") (pinfunction "PC9_66") (pintype "bidirectional"))
      (node (ref "K3") (pin "8") (pinfunction "DAT1_8") (pintype "bidirectional"))
      (node (ref "R18") (pin "P$1") (pinfunction "1_P$1") (pintype "passive"))
    )
    (net (code "37") (name "Net-(IC2-PC10)") (class "Default")
      (node (ref "IC2") (pin "78") (pinfunction "PC10_78") (pintype "bidirectional"))
      (node (ref "K3") (pin "1") (pinfunction "DAT2_1") (pintype "bidirectional"))
      (node (ref "R19") (pin "P$1") (pinfunction "1_P$1") (pintype "passive"))
    )
    (net (code "38") (name "Net-(IC2-PC11)") (class "Default")
      (node (ref "IC2") (pin "79") (pinfunction "PC11_79") (pintype "bidirectional"))
      (node (ref "K3") (pin "2") (pinfunction "CD/DAT3_2") (pintype "bidirectional"))
      (node (ref "R20") (pin "P$1") (pinfunction "1_P$1") (pintype "passive"))
    )
    (net (code "39") (name "Net-(IC2-PC12)") (class "Default")
      (node (ref "IC2") (pin "80") (pinfunction "PC12_80") (pintype "bidirectional"))
      (node (ref "K3") (pin "5") (pinfunction "CLK_5") (pintype "bidirectional"))
      (node (ref "R22") (pin "P$1") (pinfunction "1_P$1") (pintype "passive"))
    )
    (net (code "40") (name "Net-(IC2-PC13)") (class "Default")
      (node (ref "IC2") (pin "7") (pinfunction "PC13_7") (pintype "bidirectional"))
      (node (ref "K3") (pin "CD") (pinfunction "CD_CD") (pintype "bidirectional"))
    )
    (net (code "41") (name "Net-(IC2-PC14)") (class "Default")
      (node (ref "IC2") (pin "8") (pinfunction "PC14_8") (pintype "bidirectional"))
      (node (ref "K4") (pin "2") (pinfunction "~{RESET}_2") (pintype "bidirectional"))
    )
    (net (code "42") (name "Net-(IC2-PD0)") (class "Default")
      (node (ref "IC2") (pin "81") (pinfunction "PD0_81") (pintype "bidirectional"))
      (node (ref "K4") (pin "10") (pinfunction "DB2_10") (pintype "bidirectional"))
    )
    (net (code "43") (name "Net-(IC2-PD1)") (class "Default")
      (node (ref "IC2") (pin "82") (pinfunction "PD1_82") (pintype "bidirectional"))
      (node (ref "K4") (pin "9") (pinfunction "DB3_9") (pintype "bidirectional"))
    )
    (net (code "44") (name "Net-(IC2-PD2)") (class "Default")
      (node (ref "IC2") (pin "83") (pinfunction "PD2_83") (pintype "bidirectional"))
      (node (ref "K3") (pin "3") (pinfunction "CMD_3") (pintype "bidirectional"))
      (node (ref "R21") (pin "P$1") (pinfunction "1_P$1") (pintype "passive"))
    )
    (net (code "45") (name "Net-(IC2-PD4)") (class "Default")
      (node (ref "IC2") (pin "85") (pinfunction "PD4_85") (pintype "bidirectional"))
      (node (ref "K4") (pin "14") (pinfunction "~{RD}_14") (pintype "bidirectional"))
    )
    (net (code "46") (name "Net-(IC2-PD5)") (class "Default")
      (node (ref "IC2") (pin "86") (pinfunction "PD5_86") (pintype "bidirectional"))
      (node (ref "K4") (pin "15") (pinfunction "~{WR}_15") (pintype "bidirectional"))
    )
    (net (code "47") (name "Net-(IC2-PD7)") (class "Default")
      (node (ref "IC2") (pin "88") (pinfunction "PD7_88") (pintype "bidirectional"))
      (node (ref "K4") (pin "17") (pinfunction "~{CS}_17") (pintype "bidirectional"))
    )
    (net (code "48") (name "Net-(IC2-PD11)") (class "Default")
      (node (ref "IC2") (pin "58") (pinfunction "PD11_58") (pintype "bidirectional"))
      (node (ref "K4") (pin "16") (pinfunction "RS_16") (pintype "bidirectional"))
    )
    (net (code "49") (name "Net-(IC2-PD12)") (class "Default")
      (node (ref "IC2") (pin "59") (pinfunction "PD12_59") (pintype "bidirectional"))
      (node (ref "K4") (pin "19") (pinfunction "FMARK_19") (pintype "bidirectional"))
    )
    (net (code "50") (name "Net-(IC2-PD14)") (class "Default")
      (node (ref "IC2") (pin "61") (pinfunction "PD14_61") (pintype "bidirectional"))
      (node (ref "K4") (pin "12") (pinfunction "DB0_12") (pintype "bidirectional"))
    )
    (net (code "51") (name "Net-(IC2-PD15)") (class "Default")
      (node (ref "IC2") (pin "62") (pinfunction "PD15_62") (pintype "bidirectional"))
      (node (ref "K4") (pin "11") (pinfunction "DB1_11") (pintype "bidirectional"))
    )
    (net (code "52") (name "Net-(IC2-PE7)") (class "Default")
      (node (ref "IC2") (pin "38") (pinfunction "PE7_38") (pintype "bidirectional"))
      (node (ref "K4") (pin "8") (pinfunction "DB4_8") (pintype "bidirectional"))
    )
    (net (code "53") (name "Net-(IC2-PE8)") (class "Default")
      (node (ref "IC2") (pin "39") (pinfunction "PE8_39") (pintype "bidirectional"))
      (node (ref "K4") (pin "7") (pinfunction "DB5_7") (pintype "bidirectional"))
    )
    (net (code "54") (name "Net-(IC2-PE9)") (class "Default")
      (node (ref "IC2") (pin "40") (pinfunction "PE9_40") (pintype "bidirectional"))
      (node (ref "K4") (pin "6") (pinfunction "DB6_6") (pintype "bidirectional"))
    )
    (net (code "55") (name "Net-(IC2-PE10)") (class "Default")
      (node (ref "IC2") (pin "41") (pinfunction "PE10_41") (pintype "bidirectional"))
      (node (ref "K4") (pin "5") (pinfunction "DB7_5") (pintype "bidirectional"))
    )
    (net (code "56") (name "Net-(IC2-PE11)") (class "Default")
      (node (ref "IC2") (pin "42") (pinfunction "PE11_42") (pintype "bidirectional"))
      (node (ref "K4") (pin "4") (pinfunction "DB8_4") (pintype "bidirectional"))
    )
    (net (code "57") (name "Net-(IC2-VCAP_1)") (class "Default")
      (node (ref "C13") (pin "2") (pinfunction "2_2") (pintype "passive"))
      (node (ref "IC2") (pin "49") (pinfunction "VCAP_1_49") (pintype "power_in"))
    )
    (net (code "58") (name "Net-(IC2-VCAP_2)") (class "Default")
      (node (ref "C12") (pin "2") (pinfunction "2_2") (pintype "passive"))
      (node (ref "IC2") (pin "73") (pinfunction "VCAP_2_73") (pintype "power_in"))
    )
    (net (code "59") (name "Net-(IC5-CTRL)") (class "Default")
      (node (ref "IC5") (pin "5") (pinfunction "CTRL_5") (pintype "input"))
      (node (ref "R10") (pin "P$2") (pinfunction "2_P$2") (pintype "passive"))
      (node (ref "R9") (pin "P$2") (pinfunction "2_P$2") (pintype "passive"))
      (node (ref "TP6") (pin "1") (pinfunction "1_1") (pintype "passive"))
    )
    (net (code "60") (name "Net-(IC5-FB)") (class "Default")
      (node (ref "IC5") (pin "2") (pinfunction "RS_2") (pintype "passive"))
      (node (ref "IC5") (pin "4") (pinfunction "FB_4") (pintype "power_in"))
      (node (ref "R14") (pin "P$2") (pinfunction "2_P$2") (pintype "passive"))
    )
    (net (code "61") (name "Net-(IC5-OVP)") (class "Default")
      (node (ref "IC5") (pin "7") (pinfunction "OVP_7") (pintype "input"))
      (node (ref "R25") (pin "P$2") (pinfunction "2_P$2") (pintype "passive"))
      (node (ref "R26") (pin "P$1") (pinfunction "1_P$1") (pintype "passive"))
    )
    (net (code "62") (name "Net-(K6-EINT)") (class "Default")
      (node (ref "K6") (pin "4") (pinfunction "EINT_4") (pintype "bidirectional"))
      (node (ref "R13") (pin "P$1") (pinfunction "1_P$1") (pintype "passive"))
    )
    (net (code "63") (name "PWM") (class "Default")
      (node (ref "IC2") (pin "32") (pinfunction "PA7/SPI1_MOSI_32") (pintype "bidirectional"))
      (node (ref "R10") (pin "P$1") (pinfunction "1_P$1") (pintype "passive"))
    )
    (net (code "64") (name "REST") (class "Default")
      (node (ref "IC2") (pin "34") (pinfunction "PC5_34") (pintype "bidirectional"))
      (node (ref "K6") (pin "5") (pinfunction "REST_5") (pintype "bidirectional"))
      (node (ref "R12") (pin "P$2") (pinfunction "2_P$2") (pintype "passive"))
    )
    (net (code "65") (name "SBU1") (class "Default")
      (node (ref "D2") (pin "2") (pinfunction "2_2") (pintype "passive"))
      (node (ref "IC2") (pin "25") (pinfunction "PA2_25") (pintype "bidirectional"))
      (node (ref "K1") (pin "A8") (pinfunction "SBU1_A8") (pintype "passive"))
      (node (ref "TP10") (pin "1") (pinfunction "1_1") (pintype "passive"))
    )
    (net (code "66") (name "SBU2") (class "Default")
      (node (ref "D4") (pin "2") (pinfunction "2_2") (pintype "passive"))
      (node (ref "IC2") (pin "26") (pinfunction "PA3_26") (pintype "bidirectional"))
      (node (ref "K1") (pin "B8") (pinfunction "SBU2_B8") (pintype "passive"))
      (node (ref "TP11") (pin "1") (pinfunction "1_1") (pintype "passive"))
    )
    (net (code "67") (name "SD_ON") (class "Default")
      (node (ref "IC2") (pin "15") (pinfunction "PC0_15") (pintype "bidirectional"))
      (node (ref "R3") (pin "P$1") (pinfunction "1_P$1") (pintype "passive"))
    )
    (net (code "68") (name "TOUCH_ON") (class "Default")
      (node (ref "IC2") (pin "47") (pinfunction "PB10_47") (pintype "bidirectional"))
      (node (ref "R24") (pin "P$2") (pinfunction "2_P$2") (pintype "passive"))
    )
    (net (code "69") (name "VBUS") (class "Default")
      (node (ref "D1") (pin "A") (pinfunction "1_A") (pintype "passive"))
      (node (ref "D3") (pin "4") (pinfunction "VCC_4") (pintype "passive"))
      (node (ref "K1") (pin "A4") (pinfunction "VBUS_A4") (pintype "passive"))
      (node (ref "K1") (pin "A9") (pinfunction "VBUS_A9") (pintype "passive"))
      (node (ref "K1") (pin "B4") (pinfunction "VBUS_B4") (pintype "passive"))
      (node (ref "K1") (pin "B9") (pinfunction "VBUS_B9") (pintype "passive"))
    )
    (net (code "70") (name "VCC") (class "Default")
      (node (ref "C14") (pin "1") (pinfunction "1_1") (pintype "passive"))
      (node (ref "C16") (pin "P$2") (pinfunction "2_P$2") (pintype "passive"))
      (node (ref "C4") (pin "2") (pinfunction "2_2") (pintype "passive"))
      (node (ref "IC5") (pin "3") (pinfunction "VIN_3") (pintype "input"))
      (node (ref "IC6") (pin "1") (pinfunction "CE_1") (pintype "passive"))
      (node (ref "IC6") (pin "4") (pinfunction "IN_4") (pintype "passive"))
      (node (ref "L1") (pin "1") (pinfunction "1_1") (pintype "passive"))
      (node (ref "R1") (pin "P$2") (pinfunction "2_P$2") (pintype "passive"))
      (node (ref "R8") (pin "1") (pinfunction "1_1") (pintype "passive"))
      (node (ref "TP5") (pin "1") (pinfunction "1_1") (pintype "passive"))
    )
    (net (code "71") (name "VDD") (class "Default")
      (node (ref "C19") (pin "2") (pinfunction "2_2") (pintype "passive"))
      (node (ref "C24") (pin "P$2") (pinfunction "2_P$2") (pintype "passive"))
      (node (ref "C49") (pin "P$2") (pinfunction "2_P$2") (pintype "passive"))
      (node (ref "K6") (pin "1") (pinfunction "VDD_1") (pintype "power_in"))
      (node (ref "L3") (pin "2") (pinfunction "2_2") (pintype "passive"))
      (node (ref "R12") (pin "P$1") (pinfunction "1_P$1") (pintype "passive"))
      (node (ref "R15") (pin "P$2") (pinfunction "2_P$2") (pintype "passive"))
      (node (ref "R16") (pin "P$2") (pinfunction "2_P$2") (pintype "passive"))
      (node (ref "TP16") (pin "1") (pinfunction "1_1") (pintype "passive"))
    )
    (net (code "72") (name "unconnected-(IC2-PA0-WKUP-Pad23)") (class "Default")
      (node (ref "IC2") (pin "23") (pinfunction "PA0-WKUP_23") (pintype "bidirectional"))
    )
    (net (code "73") (name "unconnected-(IC2-PA1-Pad24)") (class "Default")
      (node (ref "IC2") (pin "24") (pinfunction "PA1_24") (pintype "bidirectional"))
    )
    (net (code "74") (name "unconnected-(IC2-PA4{slash}SPI1_NSS{slash}OTG_HS_SOF-Pad29)") (class "Default")
      (node (ref "IC2") (pin "29") (pinfunction "PA4/SPI1_NSS/OTG_HS_SOF_29") (pintype "bidirectional"))
    )
    (net (code "75") (name "unconnected-(IC2-PA5{slash}SPI1_SCK-Pad30)") (class "Default")
      (node (ref "IC2") (pin "30") (pinfunction "PA5/SPI1_SCK_30") (pintype "bidirectional"))
    )
    (net (code "76") (name "unconnected-(IC2-PA6{slash}SPI1_MISO-Pad31)") (class "Default")
      (node (ref "IC2") (pin "31") (pinfunction "PA6/SPI1_MISO_31") (pintype "bidirectional"))
    )
    (net (code "77") (name "unconnected-(IC2-PA8{slash}OTG_FS_SOF-Pad67)") (class "Default")
      (node (ref "IC2") (pin "67") (pinfunction "PA8/OTG_FS_SOF_67") (pintype "bidirectional"))
    )
    (net (code "78") (name "unconnected-(IC2-PA9{slash}OTG_FS_VBUS-Pad68)") (class "Default")
      (node (ref "IC2") (pin "68") (pinfunction "PA9/OTG_FS_VBUS_68") (pintype "bidirectional"))
    )
    (net (code "79") (name "unconnected-(IC2-PA10{slash}OFG_FS_ID-Pad69)") (class "Default")
      (node (ref "IC2") (pin "69") (pinfunction "PA10/OFG_FS_ID_69") (pintype "bidirectional"))
    )
    (net (code "80") (name "unconnected-(IC2-PA11{slash}OTG_FS_DM-Pad70)") (class "Default")
      (node (ref "IC2") (pin "70") (pinfunction "PA11/OTG_FS_DM_70") (pintype "bidirectional"))
    )
    (net (code "81") (name "unconnected-(IC2-PA12{slash}OTG_FS_DP-Pad71)") (class "Default")
      (node (ref "IC2") (pin "71") (pinfunction "PA12/OTG_FS_DP_71") (pintype "bidirectional"))
    )
    (net (code "82") (name "unconnected-(IC2-PA15-Pad77)") (class "Default")
      (node (ref "IC2") (pin "77") (pinfunction "PA15_77") (pintype "bidirectional"))
    )
    (net (code "83") (name "unconnected-(IC2-PB0-Pad35)") (class "Default")
      (node (ref "IC2") (pin "35") (pinfunction "PB0_35") (pintype "bidirectional"))
    )
    (net (code "84") (name "unconnected-(IC2-PB1-Pad36)") (class "Default")
      (node (ref "IC2") (pin "36") (pinfunction "PB1_36") (pintype "bidirectional"))
    )
    (net (code "85") (name "unconnected-(IC2-PB2-Pad37)") (class "Default")
      (node (ref "IC2") (pin "37") (pinfunction "PB2_37") (pintype "bidirectional"))
    )
    (net (code "86") (name "unconnected-(IC2-PB4-Pad90)") (class "Default")
      (node (ref "IC2") (pin "90") (pinfunction "PB4_90") (pintype "bidirectional"))
    )
    (net (code "87") (name "unconnected-(IC2-PB5-Pad91)") (class "Default")
      (node (ref "IC2") (pin "91") (pinfunction "PB5_91") (pintype "bidirectional"))
    )
    (net (code "88") (name "unconnected-(IC2-PB8-Pad95)") (class "Default")
      (node (ref "IC2") (pin "95") (pinfunction "PB8_95") (pintype "bidirectional"))
    )
    (net (code "89") (name "unconnected-(IC2-PB9-Pad96)") (class "Default")
      (node (ref "IC2") (pin "96") (pinfunction "PB9_96") (pintype "bidirectional"))
    )
    (net (code "90") (name "unconnected-(IC2-PB11-Pad48)") (class "Default")
      (node (ref "IC2") (pin "48") (pinfunction "PB11_48") (pintype "bidirectional"))
    )
    (net (code "91") (name "unconnected-(IC2-PB12{slash}OTG_HS_ID-Pad51)") (class "Default")
      (node (ref "IC2") (pin "51") (pinfunction "PB12/OTG_HS_ID_51") (pintype "bidirectional"))
    )
    (net (code "92") (name "unconnected-(IC2-PC1-Pad16)") (class "Default")
      (node (ref "IC2") (pin "16") (pinfunction "PC1_16") (pintype "bidirectional"))
    )
    (net (code "93") (name "unconnected-(IC2-PC2-Pad17)") (class "Default")
      (node (ref "IC2") (pin "17") (pinfunction "PC2_17") (pintype "bidirectional"))
    )
    (net (code "94") (name "unconnected-(IC2-PC3-Pad18)") (class "Default")
      (node (ref "IC2") (pin "18") (pinfunction "PC3_18") (pintype "bidirectional"))
    )
    (net (code "95") (name "unconnected-(IC2-PC6-Pad63)") (class "Default")
      (node (ref "IC2") (pin "63") (pinfunction "PC6_63") (pintype "bidirectional"))
    )
    (net (code "96") (name "unconnected-(IC2-PC7-Pad64)") (class "Default")
      (node (ref "IC2") (pin "64") (pinfunction "PC7_64") (pintype "bidirectional"))
    )
    (net (code "97") (name "unconnected-(IC2-PC15-Pad9)") (class "Default")
      (node (ref "IC2") (pin "9") (pinfunction "PC15_9") (pintype "bidirectional"))
    )
    (net (code "98") (name "unconnected-(IC2-PD3-Pad84)") (class "Default")
      (node (ref "IC2") (pin "84") (pinfunction "PD3_84") (pintype "bidirectional"))
    )
    (net (code "99") (name "unconnected-(IC2-PD6-Pad87)") (class "Default")
      (node (ref "IC2") (pin "87") (pinfunction "PD6_87") (pintype "bidirectional"))
    )
    (net (code "100") (name "unconnected-(IC2-PD8-Pad55)") (class "Default")
      (node (ref "IC2") (pin "55") (pinfunction "PD8_55") (pintype "bidirectional"))
    )
    (net (code "101") (name "unconnected-(IC2-PD9-Pad56)") (class "Default")
      (node (ref "IC2") (pin "56") (pinfunction "PD9_56") (pintype "bidirectional"))
    )
    (net (code "102") (name "unconnected-(IC2-PD10-Pad57)") (class "Default")
      (node (ref "IC2") (pin "57") (pinfunction "PD10_57") (pintype "bidirectional"))
    )
    (net (code "103") (name "unconnected-(IC2-PD13-Pad60)") (class "Default")
      (node (ref "IC2") (pin "60") (pinfunction "PD13_60") (pintype "bidirectional"))
    )
    (net (code "104") (name "unconnected-(IC2-PE0-Pad97)") (class "Default")
      (node (ref "IC2") (pin "97") (pinfunction "PE0_97") (pintype "bidirectional"))
    )
    (net (code "105") (name "unconnected-(IC2-PE1-Pad98)") (class "Default")
      (node (ref "IC2") (pin "98") (pinfunction "PE1_98") (pintype "bidirectional"))
    )
    (net (code "106") (name "unconnected-(IC2-PE2-Pad1)") (class "Default")
      (node (ref "IC2") (pin "1") (pinfunction "PE2_1") (pintype "bidirectional"))
    )
    (net (code "107") (name "unconnected-(IC2-PE3-Pad2)") (class "Default")
      (node (ref "IC2") (pin "2") (pinfunction "PE3_2") (pintype "bidirectional"))
    )
    (net (code "108") (name "unconnected-(IC2-PE4-Pad3)") (class "Default")
      (node (ref "IC2") (pin "3") (pinfunction "PE4_3") (pintype "bidirectional"))
    )
    (net (code "109") (name "unconnected-(IC2-PE5-Pad4)") (class "Default")
      (node (ref "IC2") (pin "4") (pinfunction "PE5_4") (pintype "bidirectional"))
    )
    (net (code "110") (name "unconnected-(IC2-PE6-Pad5)") (class "Default")
      (node (ref "IC2") (pin "5") (pinfunction "PE6_5") (pintype "bidirectional"))
    )
    (net (code "111") (name "unconnected-(IC2-PE12-Pad43)") (class "Default")
      (node (ref "IC2") (pin "43") (pinfunction "PE12_43") (pintype "bidirectional"))
    )
    (net (code "112") (name "unconnected-(IC2-PE13-Pad44)") (class "Default")
      (node (ref "IC2") (pin "44") (pinfunction "PE13_44") (pintype "bidirectional"))
    )
    (net (code "113") (name "unconnected-(IC2-PE14-Pad45)") (class "Default")
      (node (ref "IC2") (pin "45") (pinfunction "PE14_45") (pintype "bidirectional"))
    )
    (net (code "114") (name "unconnected-(IC2-PE15-Pad46)") (class "Default")
      (node (ref "IC2") (pin "46") (pinfunction "PE15_46") (pintype "bidirectional"))
    )
    (net (code "115") (name "unconnected-(IC6-NC-Pad3)") (class "Default")
      (node (ref "IC6") (pin "3") (pinfunction "NC_3") (pintype "passive"))
    )
    (net (code "116") (name "unconnected-(K1-RX1+-PadB11)") (class "Default")
      (node (ref "K1") (pin "B11") (pinfunction "RX1+_B11") (pintype "passive"))
    )
    (net (code "117") (name "unconnected-(K1-RX1--PadB10)") (class "Default")
      (node (ref "K1") (pin "B10") (pinfunction "RX1-_B10") (pintype "passive"))
    )
    (net (code "118") (name "unconnected-(K1-RX2+-PadA11)") (class "Default")
      (node (ref "K1") (pin "A11") (pinfunction "RX2+_A11") (pintype "passive"))
    )
    (net (code "119") (name "unconnected-(K1-RX2--PadA10)") (class "Default")
      (node (ref "K1") (pin "A10") (pinfunction "RX2-_A10") (pintype "passive"))
    )
    (net (code "120") (name "unconnected-(K1-TX1+-PadA2)") (class "Default")
      (node (ref "K1") (pin "A2") (pinfunction "TX1+_A2") (pintype "passive"))
    )
    (net (code "121") (name "unconnected-(K1-TX1--PadA3)") (class "Default")
      (node (ref "K1") (pin "A3") (pinfunction "TX1-_A3") (pintype "passive"))
    )
    (net (code "122") (name "unconnected-(K1-TX2+-PadB2)") (class "Default")
      (node (ref "K1") (pin "B2") (pinfunction "TX2+_B2") (pintype "passive"))
    )
    (net (code "123") (name "unconnected-(K1-TX2--PadB3)") (class "Default")
      (node (ref "K1") (pin "B3") (pinfunction "TX2-_B3") (pintype "passive"))
    )
    (net (code "124") (name "unconnected-(K6-NC-Pad8)") (class "Default")
      (node (ref "K6") (pin "8") (pinfunction "NC_8") (pintype "passive"))
    )
  )
)
